# x-talk.net
KiCad netlist of a schematic drawn in EAGLE
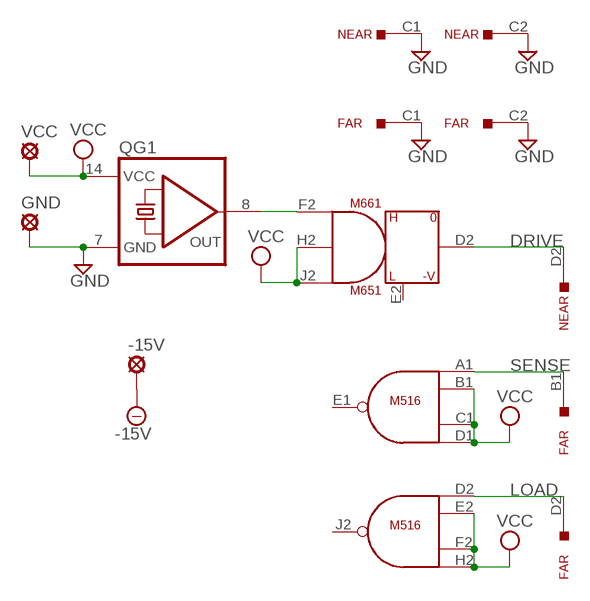
[diagram p0: schematic, sheet 1]

(export (version "E")
  (design (tool "Eeschema 10.0.6"))
  (components
    (comp (ref "-15V")
      (value "SE11")
      (footprint "eagle-import:SE11")
      (libsource (lib "eagle-import") (part "SE11"))
    )
    (comp (ref "FAR")
      (value "M916")
      (footprint "eagle-import:H807")
      (libsource (lib "eagle-import") (part "M916"))
    )
    (comp (ref "GND")
      (value "SE11")
      (footprint "eagle-import:SE11")
      (libsource (lib "eagle-import") (part "SE11"))
    )
    (comp (ref "M516")
      (value "M117")
      (footprint "eagle-import:H807")
      (libsource (lib "eagle-import") (part "M117"))
    )
    (comp (ref "M661")
      (value "M651")
      (footprint "eagle-import:H807")
      (libsource (lib "eagle-import") (part "M651"))
    )
    (comp (ref "NEAR")
      (value "M916")
      (footprint "eagle-import:H807")
      (libsource (lib "eagle-import") (part "M916"))
    )
    (comp (ref "QG1")
      (value "QG5860")
      (footprint "eagle-import:DIL14S")
      (libsource (lib "eagle-import") (part "QG5860"))
    )
    (comp (ref "VCC")
      (value "SE11")
      (footprint "eagle-import:SE11")
      (libsource (lib "eagle-import") (part "SE11"))
    )
  )
  (nets
    (net (code "1") (name "-15V") (class "Default")
      (node (ref "-15V") (pin "MP") (pinfunction "MP_MP") (pintype "passive"))
    )
    (net (code "2") (name "/DRIVE") (class "Default")
      (node (ref "M661") (pin "D2") (pinfunction "OUT_D2") (pintype "output"))
      (node (ref "NEAR") (pin "D2") (pinfunction "P$2_D2") (pintype "bidirectional"))
    )
    (net (code "3") (name "/LOAD") (class "Default")
      (node (ref "FAR") (pin "D2") (pinfunction "P$2_D2") (pintype "bidirectional"))
      (node (ref "M516") (pin "D2") (pinfunction "IN1_D2") (pintype "input"))
    )
    (net (code "4") (name "/SENSE") (class "Default")
      (node (ref "FAR") (pin "B1") (pinfunction "P$2_B1") (pintype "bidirectional"))
      (node (ref "M516") (pin "A1") (pinfunction "IN1_A1") (pintype "input"))
    )
    (net (code "5") (name "GND") (class "Default")
      (node (ref "FAR") (pin "C1") (pinfunction "P$2_C1") (pintype "bidirectional"))
      (node (ref "FAR") (pin "C2") (pinfunction "P$2_C2") (pintype "bidirectional"))
      (node (ref "GND") (pin "MP") (pinfunction "MP_MP") (pintype "passive"))
      (node (ref "NEAR") (pin "C1") (pinfunction "P$2_C1") (pintype "bidirectional"))
      (node (ref "NEAR") (pin "C2") (pinfunction "P$2_C2") (pintype "bidirectional"))
      (node (ref "QG1") (pin "7") (pinfunction "GND_7") (pintype "power_in"))
    )
    (net (code "6") (name "Net-(M661A-IN1)") (class "Default")
      (node (ref "M661") (pin "F2") (pinfunction "IN1_F2") (pintype "input"))
      (node (ref "QG1") (pin "8") (pinfunction "OUT_8") (pintype "output"))
    )
    (net (code "7") (name "VCC") (class "Default")
      (node (ref "M516") (pin "B1") (pinfunction "IN2_B1") (pintype "input"))
      (node (ref "M516") (pin "C1") (pinfunction "IN3_C1") (pintype "input"))
      (node (ref "M516") (pin "D1") (pinfunction "IN4_D1") (pintype "input"))
      (node (ref "M516") (pin "E2") (pinfunction "IN2_E2") (pintype "input"))
      (node (ref "M516") (pin "F2") (pinfunction "IN3_F2") (pintype "input"))
      (node (ref "M516") (pin "H2") (pinfunction "IN4_H2") (pintype "input"))
      (node (ref "M661") (pin "H2") (pinfunction "IN2_H2") (pintype "input"))
      (node (ref "M661") (pin "J2") (pinfunction "IN3_J2") (pintype "input"))
      (node (ref "QG1") (pin "14") (pinfunction "VCC_14") (pintype "power_in"))
      (node (ref "VCC") (pin "MP") (pinfunction "MP_MP") (pintype "passive"))
    )
    (net (code "8") (name "unconnected-(M516A-OUT-PadE1)") (class "Default")
      (node (ref "M516") (pin "E1") (pinfunction "OUT_E1") (pintype "output"))
    )
    (net (code "9") (name "unconnected-(M516D-OUT-PadJ2)") (class "Default")
      (node (ref "M516") (pin "J2") (pinfunction "OUT_J2") (pintype "output"))
    )
    (net (code "10") (name "unconnected-(M661A-SLOW-PadE2)") (class "Default")
      (node (ref "M661") (pin "E2") (pinfunction "SLOW_E2") (pintype "passive"))
    )
  )
)
